# Tiles_Proto3_RevB.net
KiCad netlist of a schematic drawn in EAGLE
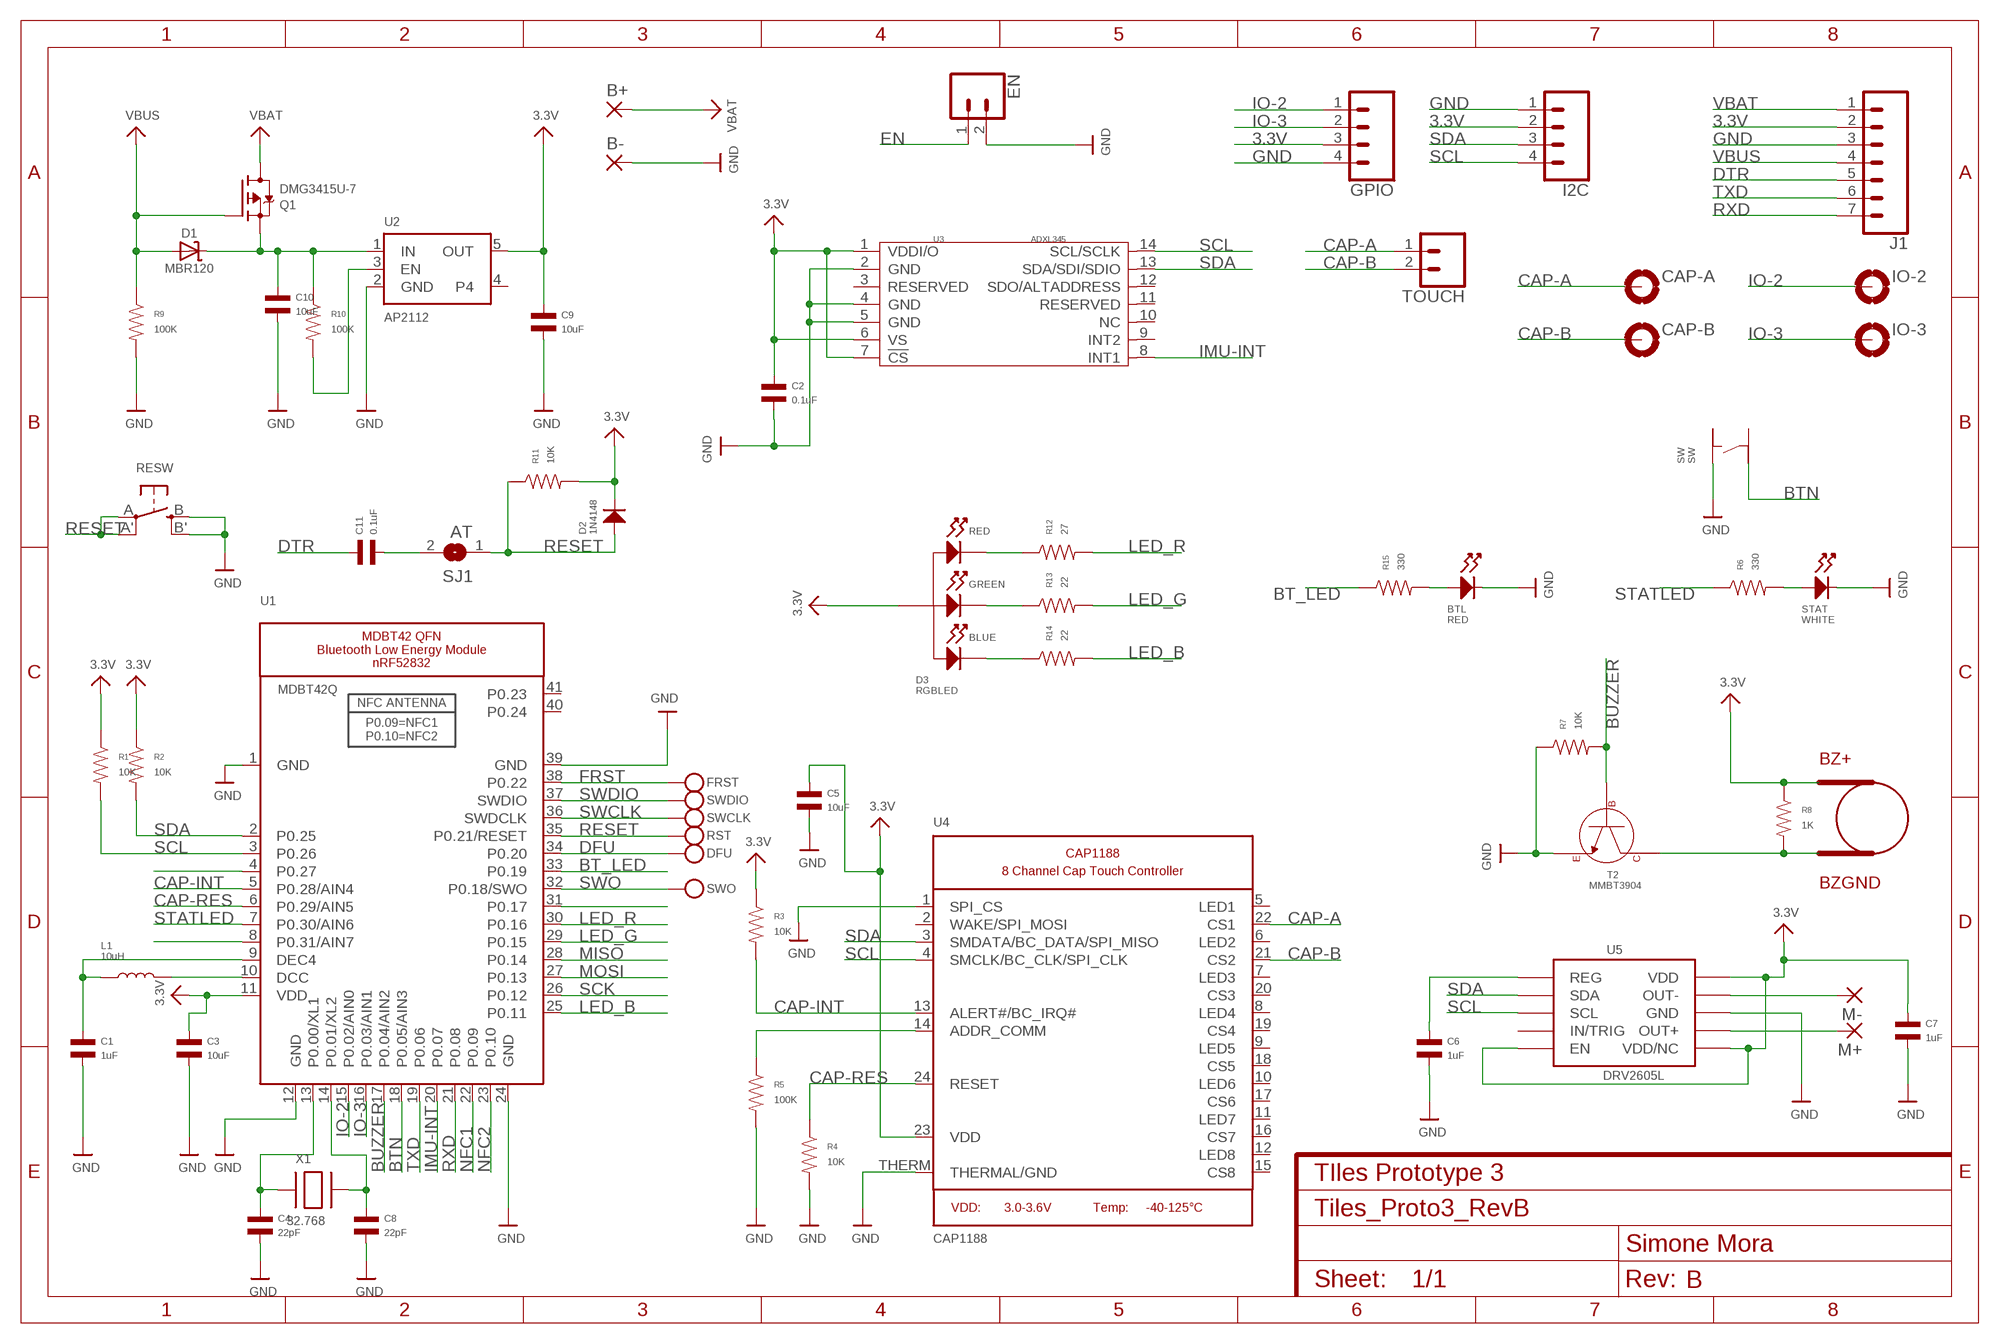
[diagram p0: schematic, sheet 1]

(export (version "E")
  (design (tool "Eeschema 10.0.6"))
  (components
    (comp (ref "B+")
      (value "SMD2")
      (footprint "eagle-import:SMD1,27-2,54")
      (libsource (lib "eagle-import") (part "SMD2"))
    )
    (comp (ref "B-")
      (value "SMD2")
      (footprint "eagle-import:SMD1,27-2,54")
      (libsource (lib "eagle-import") (part "SMD2"))
    )
    (comp (ref "BTL")
      (value "RED")
      (footprint "eagle-import:LED0603")
      (fields (field (name "HOUSEPART") "YES") (field (name "MPN") "MF-LED-0603-RED"))
      (libsource (lib "eagle-import") (part "LED_SINGLE-0603-RED"))
    )
    (comp (ref "BUZZER")
      (value "4MBUZ")
      (footprint "eagle-import:BUZPKG")
      (fields (field (name "HOUSEPART") "no") (field (name "MPN") "490-CMT-4023S-SMT-TR"))
      (libsource (lib "eagle-import") (part "4MBUZ"))
    )
    (comp (ref "C1")
      (value "1uF")
      (footprint "eagle-import:C0603")
      (fields (field (name "HOUSEPART") "YES") (field (name "MPN") "MF-CAP-0603-1uF"))
      (libsource (lib "eagle-import") (part "CAPACITOR_NP_0603"))
    )
    (comp (ref "C2")
      (value "0.1uF")
      (footprint "eagle-import:C0603")
      (fields (field (name "HOUSEPART") "YES") (field (name "MPN") "MF-CAP-0603-0.1uF"))
      (libsource (lib "eagle-import") (part "CAPACITOR_NP_0603"))
    )
    (comp (ref "C3")
      (value "10uF")
      (footprint "eagle-import:C1206")
      (fields (field (name "HOUSEPART") "YES") (field (name "MPN") "MF-CAP-1206-10uF"))
      (libsource (lib "eagle-import") (part "CAPACITOR_NP_1206"))
    )
    (comp (ref "C4")
      (value "22pF")
      (footprint "eagle-import:C0603")
      (fields (field (name "HOUSEPART") "YES") (field (name "MPN") "MF-CAP-0603-22pF"))
      (libsource (lib "eagle-import") (part "CAPACITOR_NP_0603"))
    )
    (comp (ref "C5")
      (value "10uF")
      (footprint "eagle-import:C1206")
      (fields (field (name "HOUSEPART") "YES") (field (name "MPN") "MF-CAP-1206-10uF"))
      (libsource (lib "eagle-import") (part "CAPACITOR_NP_1206"))
    )
    (comp (ref "C6")
      (value "1uF")
      (footprint "eagle-import:C0603")
      (fields (field (name "HOUSEPART") "YES") (field (name "MPN") "MF-CAP-0603-1uF"))
      (libsource (lib "eagle-import") (part "CAPACITOR_NP_0603"))
    )
    (comp (ref "C7")
      (value "1uF")
      (footprint "eagle-import:C0603")
      (fields (field (name "HOUSEPART") "YES") (field (name "MPN") "MF-CAP-0603-1uF"))
      (libsource (lib "eagle-import") (part "CAPACITOR_NP_0603"))
    )
    (comp (ref "C8")
      (value "22pF")
      (footprint "eagle-import:C0603")
      (fields (field (name "HOUSEPART") "YES") (field (name "MPN") "MF-CAP-0603-22pF"))
      (libsource (lib "eagle-import") (part "CAPACITOR_NP_0603"))
    )
    (comp (ref "C9")
      (value "10uF")
      (footprint "eagle-import:C1206")
      (fields (field (name "HOUSEPART") "YES") (field (name "MPN") "MF-CAP-1206-10uF"))
      (libsource (lib "eagle-import") (part "CAPACITOR_NP_1206"))
    )
    (comp (ref "C10")
      (value "10uF")
      (footprint "eagle-import:C1206")
      (fields (field (name "HOUSEPART") "YES") (field (name "MPN") "MF-CAP-1206-10uF"))
      (libsource (lib "eagle-import") (part "CAPACITOR_NP_1206"))
    )
    (comp (ref "C11")
      (value "0.1uF")
      (footprint "eagle-import:C0603")
      (fields (field (name "HOUSEPART") "YES") (field (name "MPN") "MF-CAP-0603-0.1uF"))
      (libsource (lib "eagle-import") (part "CAPACITOR_NP_0603"))
    )
    (comp (ref "CAP-A")
      (value "MOUNT-PAD-ROUND2.5")
      (footprint "eagle-import:2,5-PAD-SIM")
      (libsource (lib "eagle-import") (part "MOUNT-PAD-ROUND2.5"))
    )
    (comp (ref "CAP-B")
      (value "MOUNT-PAD-ROUND2.5")
      (footprint "eagle-import:2,5-PAD-SIM")
      (libsource (lib "eagle-import") (part "MOUNT-PAD-ROUND2.5"))
    )
    (comp (ref "D1")
      (value "MBR120")
      (footprint "eagle-import:SOD-123")
      (fields (field (name "HOUSEPART") "NO") (field (name "MPN") "MBR120LSFT1G"))
      (libsource (lib "eagle-import") (part "DIODE-SCHOTTKYSOD-123"))
    )
    (comp (ref "D2")
      (value "1N4148")
      (footprint "eagle-import:SOD-123")
      (fields (field (name "HOUSEPART") "YES") (field (name "MPN") "MF-DIO-SOD123-1N4148"))
      (libsource (lib "eagle-import") (part "DIODES_SOD-123_1N4148"))
    )
    (comp (ref "D3")
      (value "RGBLED")
      (footprint "eagle-import:PLCC4")
      (fields (field (name "HOUSEPART") "YES") (field (name "MPN") "MF-LED-3228-RGB"))
      (libsource (lib "eagle-import") (part "LED_RGB_CA_PLCC4"))
    )
    (comp (ref "DFU")
      (value "TESTPOINTROUND2MM")
      (footprint "eagle-import:TESTPOINT_ROUND_2MM")
      (libsource (lib "eagle-import") (part "TESTPOINTROUND2MM"))
    )
    (comp (ref "EN")
      (value "CONN_021X02_NO_SILK")
      (footprint "eagle-import:1X02_NO_SILK")
      (libsource (lib "eagle-import") (part "CONN_021X02_NO_SILK"))
    )
    (comp (ref "FRST")
      (value "TESTPOINT1.5X2.0MM_NOCREAM")
      (footprint "eagle-import:PAD-1.5X2.0")
      (libsource (lib "eagle-import") (part "TESTPOINT1.5X2.0MM_NOCREAM"))
    )
    (comp (ref "GPIO")
      (value "CONN_041X04_NO_SILK")
      (footprint "eagle-import:1X04_NO_SILK")
      (libsource (lib "eagle-import") (part "CONN_041X04_NO_SILK"))
    )
    (comp (ref "I2C")
      (value "CONN_04_SIM1X04_NO_SILK")
      (footprint "eagle-import:1X04_NO_SILK_LNG")
      (libsource (lib "eagle-import") (part "CONN_04_SIM1X04_NO_SILK"))
    )
    (comp (ref "IO-2")
      (value "MOUNT-PAD-ROUND2.5")
      (footprint "eagle-import:2,5-PAD-SIM")
      (libsource (lib "eagle-import") (part "MOUNT-PAD-ROUND2.5"))
    )
    (comp (ref "IO-3")
      (value "MOUNT-PAD-ROUND2.5")
      (footprint "eagle-import:2,5-PAD-SIM")
      (libsource (lib "eagle-import") (part "MOUNT-PAD-ROUND2.5"))
    )
    (comp (ref "J1")
      (value "CONN_07")
      (footprint "eagle-import:1X07")
      (libsource (lib "eagle-import") (part "CONN_07"))
    )
    (comp (ref "L1")
      (value "10uH")
      (footprint "eagle-import:L1210")
      (fields
        (field (name "HOUSEPART") "YES")
        (field (name "MPN") "MF-IND-1210-10uH")
        (field (name "POPULATE") "1")
      )
      (libsource (lib "eagle-import") (part "INDUCTOR_1210"))
    )
    (comp (ref "M+")
      (value "1,6/0,8")
      (footprint "eagle-import:1,6_0,8")
      (libsource (lib "eagle-import") (part "1,6/0,8"))
    )
    (comp (ref "M-")
      (value "1,6/0,8")
      (footprint "eagle-import:1,6_0,8")
      (libsource (lib "eagle-import") (part "1,6/0,8"))
    )
    (comp (ref "Q1")
      (value "DMG3415U-7")
      (footprint "eagle-import:SOT23-R")
      (fields (field (name "HOUSEPART") "YES") (field (name "MPN") "MF-DSC-SOT233-BSS84"))
      (libsource (lib "eagle-import") (part "MOSFET-P"))
    )
    (comp (ref "R1")
      (value "10K")
      (footprint "eagle-import:R0603")
      (fields (field (name "HOUSEPART") "YES") (field (name "MPN") "MF-RES-0603-10K"))
      (libsource (lib "eagle-import") (part "RESISTOR_0603"))
    )
    (comp (ref "R2")
      (value "10K")
      (footprint "eagle-import:R0603")
      (fields (field (name "HOUSEPART") "YES") (field (name "MPN") "MF-RES-0603-10K"))
      (libsource (lib "eagle-import") (part "RESISTOR_0603"))
    )
    (comp (ref "R3")
      (value "10K")
      (footprint "eagle-import:R0603")
      (fields (field (name "HOUSEPART") "YES") (field (name "MPN") "MF-RES-0603-10K"))
      (libsource (lib "eagle-import") (part "RESISTOR_0603"))
    )
    (comp (ref "R4")
      (value "10K")
      (footprint "eagle-import:R0603")
      (fields (field (name "HOUSEPART") "YES") (field (name "MPN") "MF-RES-0603-10K"))
      (libsource (lib "eagle-import") (part "RESISTOR_0603"))
    )
    (comp (ref "R5")
      (value "100K")
      (footprint "eagle-import:R0603")
      (fields (field (name "HOUSEPART") "YES") (field (name "MPN") "MF-RES-0603-100K"))
      (libsource (lib "eagle-import") (part "RESISTOR_0603"))
    )
    (comp (ref "R6")
      (value "330")
      (footprint "eagle-import:R0603")
      (fields (field (name "HOUSEPART") "YES") (field (name "MPN") "MF-RES-0603-330"))
      (libsource (lib "eagle-import") (part "RESISTOR_0603"))
    )
    (comp (ref "R7")
      (value "10K")
      (footprint "eagle-import:R0603")
      (fields (field (name "HOUSEPART") "YES") (field (name "MPN") "MF-RES-0603-10K"))
      (libsource (lib "eagle-import") (part "RESISTOR_0603"))
    )
    (comp (ref "R8")
      (value "1K")
      (footprint "eagle-import:R0603")
      (fields (field (name "HOUSEPART") "YES") (field (name "MPN") "MF-RES-0603-1K"))
      (libsource (lib "eagle-import") (part "RESISTOR_0603"))
    )
    (comp (ref "R9")
      (value "100K")
      (footprint "eagle-import:R0603")
      (fields (field (name "HOUSEPART") "YES") (field (name "MPN") "MF-RES-0603-100K"))
      (libsource (lib "eagle-import") (part "RESISTOR_0603"))
    )
    (comp (ref "R10")
      (value "100K")
      (footprint "eagle-import:R0603")
      (fields (field (name "HOUSEPART") "YES") (field (name "MPN") "MF-RES-0603-100K"))
      (libsource (lib "eagle-import") (part "RESISTOR_0603"))
    )
    (comp (ref "R11")
      (value "10K")
      (footprint "eagle-import:R0603")
      (fields (field (name "HOUSEPART") "YES") (field (name "MPN") "MF-RES-0603-10K"))
      (libsource (lib "eagle-import") (part "RESISTOR_0603"))
    )
    (comp (ref "R12")
      (value "27")
      (footprint "eagle-import:R0603")
      (fields (field (name "HOUSEPART") "YES") (field (name "MPN") "MF-RES-0603-27"))
      (libsource (lib "eagle-import") (part "RESISTOR_0603"))
    )
    (comp (ref "R13")
      (value "22")
      (footprint "eagle-import:R0603")
      (fields (field (name "HOUSEPART") "YES") (field (name "MPN") "MF-RES-0603-22"))
      (libsource (lib "eagle-import") (part "RESISTOR_0603"))
    )
    (comp (ref "R14")
      (value "22")
      (footprint "eagle-import:R0603")
      (fields (field (name "HOUSEPART") "YES") (field (name "MPN") "MF-RES-0603-22"))
      (libsource (lib "eagle-import") (part "RESISTOR_0603"))
    )
    (comp (ref "R15")
      (value "330")
      (footprint "eagle-import:R0603")
      (fields (field (name "HOUSEPART") "YES") (field (name "MPN") "MF-RES-0603-330"))
      (libsource (lib "eagle-import") (part "RESISTOR_0603"))
    )
    (comp (ref "RESW")
      (value "SWITCH_TACT_SMT4.6X2.8")
      (footprint "eagle-import:BTN_KMR2_4.6X2.8")
      (libsource (lib "eagle-import") (part "SWITCH_TACT_SMT4.6X2.8"))
    )
    (comp (ref "RST")
      (value "TESTPOINTROUND2MM")
      (footprint "eagle-import:TESTPOINT_ROUND_2MM")
      (libsource (lib "eagle-import") (part "TESTPOINTROUND2MM"))
    )
    (comp (ref "SJ1")
      (value "AT")
      (footprint "eagle-import:SOLDERJUMPER_CLOSEDWIRE")
      (libsource (lib "eagle-import") (part "SOLDERJUMPERCLOSED"))
    )
    (comp (ref "STAT")
      (value "WHITE")
      (footprint "eagle-import:LED0603")
      (fields
        (field (name "HOUSEPART") "YES")
        (field (name "MPN") "MF-LED-0603-RED")
        (field (name "HOUSEPART_1") "NO")
        (field (name "MPN_1") "LNJ037X8ARA")
      )
      (libsource (lib "eagle-import") (part "LED_SINGLE-0603-RED"))
    )
    (comp (ref "SW")
      (value "SW")
      (footprint "eagle-import:TACT4.2MM")
      (fields (field (name "HOUSEPART") "YES") (field (name "MPN") "MF-SW-TACT-4.2MM"))
      (libsource (lib "eagle-import") (part "TACT_4.2MM"))
    )
    (comp (ref "SWCLK")
      (value "TESTPOINTROUND2MM")
      (footprint "eagle-import:TESTPOINT_ROUND_2MM")
      (libsource (lib "eagle-import") (part "TESTPOINTROUND2MM"))
    )
    (comp (ref "SWDIO")
      (value "TESTPOINTROUND2MM")
      (footprint "eagle-import:TESTPOINT_ROUND_2MM")
      (libsource (lib "eagle-import") (part "TESTPOINTROUND2MM"))
    )
    (comp (ref "SWO")
      (value "TESTPOINTROUND2MM")
      (footprint "eagle-import:TESTPOINT_ROUND_2MM")
      (libsource (lib "eagle-import") (part "TESTPOINTROUND2MM"))
    )
    (comp (ref "T2")
      (value "MMBT3904")
      (footprint "eagle-import:SOT-23-3")
      (fields (field (name "HOUSEPART") "YES") (field (name "MPN") "MF-DSC-SOT233-MMBT3904"))
      (libsource (lib "eagle-import") (part "NPN_BJT_SOT-23-3MMBT3904"))
    )
    (comp (ref "TOUCH")
      (value "CONN_021X02_NO_SILK")
      (footprint "eagle-import:1X02_NO_SILK")
      (libsource (lib "eagle-import") (part "CONN_021X02_NO_SILK"))
    )
    (comp (ref "U1")
      (value "MDBT42Q")
      (footprint "eagle-import:BLE_MODULE_RAYTAC_MDBT42")
      (fields (field (name "HOUSEPART") "NO") (field (name "MPN") "317030213"))
      (libsource (lib "eagle-import") (part "NRF52832_MODULE_MDBT42"))
    )
    (comp (ref "U2")
      (value "AP2112")
      (footprint "eagle-import:SOT23-5")
      (fields (field (name "HOUSEPART") "NO") (field (name "MPN") "AP2112K-3.3TRG1"))
      (libsource (lib "eagle-import") (part "VREG_SOT23-5"))
    )
    (comp (ref "U3")
      (value "ADXL345")
      (footprint "eagle-import:LGA14-0.8-5.0X3.0MM")
      (fields (field (name "MPN") "ADXL345BCCZ-RL") (field (name "HOUSEPART") "no"))
      (libsource (lib "eagle-import") (part "MOTION/POSITION-ADXL345BCCZ-RL(14P-5.0X3.0MM)"))
    )
    (comp (ref "U4")
      (value "CAP1188")
      (footprint "eagle-import:QFN24_4MM_SMSC")
      (fields (field (name "HOUSEPART") "NO") (field (name "MPN") "CAP1188-1-CP-TR"))
      (libsource (lib "eagle-import") (part "CAP1188"))
    )
    (comp (ref "U5")
      (value "DRV2605L")
      (footprint "eagle-import:VSSOP-10")
      (fields (field (name "HOUSEPART") "NO") (field (name "MPN") "DRV2605LDGST"))
      (libsource (lib "eagle-import") (part "DRV2605L"))
    )
    (comp (ref "X1")
      (value "32.768")
      (footprint "eagle-import:XTAL3215")
      (fields (field (name "HOUSEPART") "no") (field (name "MPN") "ABS07-120-32.768KHZ-T"))
      (libsource (lib "eagle-import") (part "XTAL-3.2X1.5"))
    )
  )
  (nets
    (net (code "1") (name "/BTN") (class "Default")
      (node (ref "SW") (pin "P$3") (pinfunction "P$3_P$3") (pintype "bidirectional"))
      (node (ref "U1") (pin "18") (pinfunction "P0.05/AIN3_18") (pintype "bidirectional"))
    )
    (net (code "2") (name "/BT_LED") (class "Default")
      (node (ref "R15") (pin "P$1") (pinfunction "P$1_P$1") (pintype "passive"))
      (node (ref "U1") (pin "33") (pinfunction "P0.19_33") (pintype "bidirectional"))
    )
    (net (code "3") (name "/BUZZER") (class "Default")
      (node (ref "R7") (pin "P$2") (pinfunction "P$2_P$2") (pintype "passive"))
      (node (ref "T2") (pin "P$1") (pinfunction "BASE_P$1") (pintype "bidirectional"))
      (node (ref "U1") (pin "17") (pinfunction "P0.04/AIN2_17") (pintype "bidirectional"))
    )
    (net (code "4") (name "/CAP-A") (class "Default")
      (node (ref "CAP-A") (pin "B2,8") (pinfunction "MOUNT_B2,8") (pintype "passive"))
      (node (ref "TOUCH") (pin "1") (pinfunction "1_1") (pintype "passive"))
      (node (ref "U4") (pin "22") (pinfunction "CS1_22") (pintype "bidirectional"))
    )
    (net (code "5") (name "/CAP-B") (class "Default")
      (node (ref "CAP-B") (pin "B2,8") (pinfunction "MOUNT_B2,8") (pintype "passive"))
      (node (ref "TOUCH") (pin "2") (pinfunction "2_2") (pintype "passive"))
      (node (ref "U4") (pin "21") (pinfunction "CS2_21") (pintype "bidirectional"))
    )
    (net (code "6") (name "/CAP-INT") (class "Default")
      (node (ref "R3") (pin "P$2") (pinfunction "P$2_P$2") (pintype "passive"))
      (node (ref "U1") (pin "5") (pinfunction "P0.28/AIN4_5") (pintype "bidirectional"))
      (node (ref "U4") (pin "13") (pinfunction "ALERT#/BC_IRQ#_13") (pintype "bidirectional"))
    )
    (net (code "7") (name "/CAP-RES") (class "Default")
      (node (ref "R4") (pin "P$1") (pinfunction "P$1_P$1") (pintype "passive"))
      (node (ref "U1") (pin "6") (pinfunction "P0.29/AIN5_6") (pintype "bidirectional"))
      (node (ref "U4") (pin "24") (pinfunction "RESET_24") (pintype "input"))
    )
    (net (code "8") (name "/DFU") (class "Default")
      (node (ref "DFU") (pin "P$1") (pinfunction "P$1_P$1") (pintype "bidirectional"))
      (node (ref "U1") (pin "34") (pinfunction "P0.20_34") (pintype "bidirectional"))
    )
    (net (code "9") (name "/DTR") (class "Default")
      (node (ref "C11") (pin "P$1") (pinfunction "P$1_P$1") (pintype "passive"))
      (node (ref "J1") (pin "5") (pinfunction "5_5") (pintype "passive"))
    )
    (net (code "10") (name "/EN") (class "Default")
      (node (ref "EN") (pin "1") (pinfunction "1_1") (pintype "passive"))
      (node (ref "R10") (pin "P$2") (pinfunction "P$2_P$2") (pintype "passive"))
      (node (ref "U2") (pin "3") (pinfunction "EN_3") (pintype "input"))
    )
    (net (code "11") (name "/FRST") (class "Default")
      (node (ref "FRST") (pin "P$1") (pinfunction "P$1_P$1") (pintype "bidirectional"))
      (node (ref "U1") (pin "38") (pinfunction "P0.22_38") (pintype "bidirectional"))
    )
    (net (code "12") (name "/IMU-INT") (class "Default")
      (node (ref "U1") (pin "20") (pinfunction "P0.07_20") (pintype "bidirectional"))
      (node (ref "U3") (pin "8") (pinfunction "INT1_8") (pintype "bidirectional"))
    )
    (net (code "13") (name "/IO-2") (class "Default")
      (node (ref "GPIO") (pin "1") (pinfunction "1_1") (pintype "passive"))
      (node (ref "IO-2") (pin "B2,8") (pinfunction "MOUNT_B2,8") (pintype "passive"))
      (node (ref "U1") (pin "15") (pinfunction "P0.02/AIN0_15") (pintype "bidirectional"))
    )
    (net (code "14") (name "/IO-3") (class "Default")
      (node (ref "GPIO") (pin "2") (pinfunction "2_2") (pintype "passive"))
      (node (ref "IO-3") (pin "B2,8") (pinfunction "MOUNT_B2,8") (pintype "passive"))
      (node (ref "U1") (pin "16") (pinfunction "P0.03/AIN1_16") (pintype "bidirectional"))
    )
    (net (code "15") (name "/LED_B") (class "Default")
      (node (ref "R14") (pin "P$2") (pinfunction "P$2_P$2") (pintype "passive"))
      (node (ref "U1") (pin "25") (pinfunction "P0.11_25") (pintype "bidirectional"))
    )
    (net (code "16") (name "/LED_G") (class "Default")
      (node (ref "R13") (pin "P$2") (pinfunction "P$2_P$2") (pintype "passive"))
      (node (ref "U1") (pin "29") (pinfunction "P0.15_29") (pintype "bidirectional"))
    )
    (net (code "17") (name "/LED_R") (class "Default")
      (node (ref "R12") (pin "P$2") (pinfunction "P$2_P$2") (pintype "passive"))
      (node (ref "U1") (pin "30") (pinfunction "P0.16_30") (pintype "bidirectional"))
    )
    (net (code "18") (name "/MISO") (class "Default")
      (node (ref "U1") (pin "28") (pinfunction "P0.14_28") (pintype "bidirectional"))
    )
    (net (code "19") (name "/MOSI") (class "Default")
      (node (ref "U1") (pin "27") (pinfunction "P0.13_27") (pintype "bidirectional"))
    )
    (net (code "20") (name "/NFC1") (class "Default")
      (node (ref "U1") (pin "22") (pinfunction "P0.09_22") (pintype "bidirectional"))
    )
    (net (code "21") (name "/NFC2") (class "Default")
      (node (ref "U1") (pin "23") (pinfunction "P0.10_23") (pintype "bidirectional"))
    )
    (net (code "22") (name "/RESET") (class "Default")
      (node (ref "D2") (pin "ANODE") (pinfunction "ANODE_ANODE") (pintype "bidirectional"))
      (node (ref "R11") (pin "P$1") (pinfunction "P$1_P$1") (pintype "passive"))
      (node (ref "RESW") (pin "A") (pinfunction "P_A") (pintype "passive"))
      (node (ref "RESW") (pin "A'") (pinfunction "P1_A'") (pintype "passive"))
      (node (ref "RST") (pin "P$1") (pinfunction "P$1_P$1") (pintype "bidirectional"))
      (node (ref "SJ1") (pin "1") (pinfunction "1_1") (pintype "passive"))
      (node (ref "U1") (pin "35") (pinfunction "P0.21/RESET_35") (pintype "bidirectional"))
    )
    (net (code "23") (name "/RXD") (class "Default")
      (node (ref "J1") (pin "7") (pinfunction "7_7") (pintype "passive"))
      (node (ref "U1") (pin "21") (pinfunction "P0.08_21") (pintype "bidirectional"))
    )
    (net (code "24") (name "/SCK") (class "Default")
      (node (ref "U1") (pin "26") (pinfunction "P0.12_26") (pintype "bidirectional"))
    )
    (net (code "25") (name "/SCL") (class "Default")
      (node (ref "I2C") (pin "4") (pinfunction "4_4") (pintype "passive"))
      (node (ref "R1") (pin "P$2") (pinfunction "P$2_P$2") (pintype "passive"))
      (node (ref "U1") (pin "3") (pinfunction "P0.26_3") (pintype "bidirectional"))
      (node (ref "U3") (pin "14") (pinfunction "SCL/SCLK_14") (pintype "input"))
      (node (ref "U4") (pin "4") (pinfunction "SMCLK/BC_CLK/SPI_CLK_4") (pintype "bidirectional"))
      (node (ref "U5") (pin "P$2") (pinfunction "SCL_P$2") (pintype "bidirectional"))
    )
    (net (code "26") (name "/SDA") (class "Default")
      (node (ref "I2C") (pin "3") (pinfunction "3_3") (pintype "passive"))
      (node (ref "R2") (pin "P$2") (pinfunction "P$2_P$2") (pintype "passive"))
      (node (ref "U1") (pin "2") (pinfunction "P0.25_2") (pintype "bidirectional"))
      (node (ref "U3") (pin "13") (pinfunction "SDA/SDI/SDIO_13") (pintype "bidirectional"))
      (node (ref "U4") (pin "3") (pinfunction "SMDATA/BC_DATA/SPI_MISO_3") (pintype "bidirectional"))
      (node (ref "U5") (pin "P$3") (pinfunction "SDA_P$3") (pintype "bidirectional"))
    )
    (net (code "27") (name "/STATLED") (class "Default")
      (node (ref "R6") (pin "P$1") (pinfunction "P$1_P$1") (pintype "passive"))
      (node (ref "U1") (pin "7") (pinfunction "P0.30/AIN6_7") (pintype "bidirectional"))
    )
    (net (code "28") (name "/SWCLK") (class "Default")
      (node (ref "SWCLK") (pin "P$1") (pinfunction "P$1_P$1") (pintype "bidirectional"))
      (node (ref "U1") (pin "36") (pinfunction "SWDCLK_36") (pintype "bidirectional"))
    )
    (net (code "29") (name "/SWDIO") (class "Default")
      (node (ref "SWDIO") (pin "P$1") (pinfunction "P$1_P$1") (pintype "bidirectional"))
      (node (ref "U1") (pin "37") (pinfunction "SWDIO_37") (pintype "bidirectional"))
    )
    (net (code "30") (name "/SWO") (class "Default")
      (node (ref "SWO") (pin "P$1") (pinfunction "P$1_P$1") (pintype "bidirectional"))
      (node (ref "U1") (pin "32") (pinfunction "P0.18/SWO_32") (pintype "bidirectional"))
    )
    (net (code "31") (name "/TXD") (class "Default")
      (node (ref "J1") (pin "6") (pinfunction "6_6") (pintype "passive"))
      (node (ref "U1") (pin "19") (pinfunction "P0.06_19") (pintype "bidirectional"))
    )
    (net (code "32") (name "3.3V") (class "Default")
      (node (ref "BUZZER") (pin "BZ+") (pinfunction "BUZSIG+_BZ+") (pintype "passive"))
      (node (ref "C2") (pin "P$1") (pinfunction "P$1_P$1") (pintype "passive"))
      (node (ref "C3") (pin "P$1") (pinfunction "P$1_P$1") (pintype "passive"))
      (node (ref "C5") (pin "P$1") (pinfunction "P$1_P$1") (pintype "passive"))
      (node (ref "C7") (pin "P$1") (pinfunction "P$1_P$1") (pintype "passive"))
      (node (ref "C9") (pin "P$1") (pinfunction "P$1_P$1") (pintype "passive"))
      (node (ref "D2") (pin "CATHODE") (pinfunction "CATHODE_CATHODE") (pintype "bidirectional"))
      (node (ref "D3") (pin "P$1") (pinfunction "ANODE_P$1") (pintype "power_in"))
      (node (ref "GPIO") (pin "3") (pinfunction "3_3") (pintype "passive"))
      (node (ref "I2C") (pin "2") (pinfunction "2_2") (pintype "passive"))
      (node (ref "J1") (pin "2") (pinfunction "2_2") (pintype "passive"))
      (node (ref "R1") (pin "P$1") (pinfunction "P$1_P$1") (pintype "passive"))
      (node (ref "R11") (pin "P$2") (pinfunction "P$2_P$2") (pintype "passive"))
      (node (ref "R2") (pin "P$1") (pinfunction "P$1_P$1") (pintype "passive"))
      (node (ref "R3") (pin "P$1") (pinfunction "P$1_P$1") (pintype "passive"))
      (node (ref "R8") (pin "P$1") (pinfunction "P$1_P$1") (pintype "passive"))
      (node (ref "U1") (pin "11") (pinfunction "VDD_11") (pintype "bidirectional"))
      (node (ref "U2") (pin "5") (pinfunction "OUT_5") (pintype "power_in"))
      (node (ref "U3") (pin "1") (pinfunction "VDDI/O_1") (pintype "power_in"))
      (node (ref "U3") (pin "6") (pinfunction "VS_6") (pintype "bidirectional"))
      (node (ref "U3") (pin "7") (pinfunction "~{CS}_7") (pintype "bidirectional"))
      (node (ref "U4") (pin "23") (pinfunction "VDD_23") (pintype "power_in"))
      (node (ref "U5") (pin "P$10") (pinfunction "VDD_P$10") (pintype "bidirectional"))
      (node (ref "U5") (pin "P$5") (pinfunction "EN_P$5") (pintype "bidirectional"))
      (node (ref "U5") (pin "P$6") (pinfunction "VDD/NC_P$6") (pintype "bidirectional"))
    )
    (net (code "33") (name "GND") (class "Default")
      (node (ref "B-") (pin "1") (pinfunction "P_1") (pintype "passive"))
      (node (ref "BTL") (pin "CATHODE") (pinfunction "CATHODE_CATHODE") (pintype "power_in"))
      (node (ref "C1") (pin "P$2") (pinfunction "P$2_P$2") (pintype "passive"))
      (node (ref "C10") (pin "P$2") (pinfunction "P$2_P$2") (pintype "passive"))
      (node (ref "C2") (pin "P$2") (pinfunction "P$2_P$2") (pintype "passive"))
      (node (ref "C3") (pin "P$2") (pinfunction "P$2_P$2") (pintype "passive"))
      (node (ref "C4") (pin "P$2") (pinfunction "P$2_P$2") (pintype "passive"))
      (node (ref "C5") (pin "P$2") (pinfunction "P$2_P$2") (pintype "passive"))
      (node (ref "C6") (pin "P$2") (pinfunction "P$2_P$2") (pintype "passive"))
      (node (ref "C7") (pin "P$2") (pinfunction "P$2_P$2") (pintype "passive"))
      (node (ref "C8") (pin "P$2") (pinfunction "P$2_P$2") (pintype "passive"))
      (node (ref "C9") (pin "P$2") (pinfunction "P$2_P$2") (pintype "passive"))
      (node (ref "EN") (pin "2") (pinfunction "2_2") (pintype "passive"))
      (node (ref "GPIO") (pin "4") (pinfunction "4_4") (pintype "passive"))
      (node (ref "I2C") (pin "1") (pinfunction "1_1") (pintype "passive"))
      (node (ref "J1") (pin "3") (pinfunction "3_3") (pintype "passive"))
      (node (ref "R4") (pin "P$2") (pinfunction "P$2_P$2") (pintype "passive"))
      (node (ref "R5") (pin "P$2") (pinfunction "P$2_P$2") (pintype "passive"))
      (node (ref "R7") (pin "P$1") (pinfunction "P$1_P$1") (pintype "passive"))
      (node (ref "R9") (pin "P$2") (pinfunction "P$2_P$2") (pintype "passive"))
      (node (ref "RESW") (pin "B") (pinfunction "S_B") (pintype "passive"))
      (node (ref "RESW") (pin "B'") (pinfunction "S1_B'") (pintype "passive"))
      (node (ref "STAT") (pin "CATHODE") (pinfunction "CATHODE_CATHODE") (pintype "power_in"))
      (node (ref "SW") (pin "P$1") (pinfunction "P$1_P$1") (pintype "bidirectional"))
      (node (ref "T2") (pin "P$2") (pinfunction "EMITTER_P$2") (pintype "bidirectional"))
      (node (ref "U1") (pin "1") (pinfunction "GND_1") (pintype "bidirectional"))
      (node (ref "U1") (pin "12") (pinfunction "GND_12") (pintype "bidirectional"))
      (node (ref "U1") (pin "24") (pinfunction "GND_24") (pintype "bidirectional"))
      (node (ref "U1") (pin "39") (pinfunction "GND_39") (pintype "bidirectional"))
      (node (ref "U2") (pin "2") (pinfunction "GND_2") (pintype "power_in"))
      (node (ref "U3") (pin "2") (pinfunction "GND_2") (pintype "power_in"))
      (node (ref "U3") (pin "4") (pinfunction "GND_4") (pintype "power_in"))
      (node (ref "U3") (pin "5") (pinfunction "GND_5") (pintype "power_in"))
      (node (ref "U4") (pin "1") (pinfunction "SPI_CS_1") (pintype "input"))
      (node (ref "U4") (pin "THERM") (pinfunction "THERMAL/GND_THERM") (pintype "power_in"))
      (node (ref "U5") (pin "P$8") (pinfunction "GND_P$8") (pintype "bidirectional"))
    )
    (net (code "34") (name "Net-(BTL-PadANODE)") (class "Default")
      (node (ref "BTL") (pin "ANODE") (pinfunction "ANODE_ANODE") (pintype "power_in"))
      (node (ref "R15") (pin "P$2") (pinfunction "P$2_P$2") (pintype "passive"))
    )
    (net (code "35") (name "Net-(BUZZER-BUZGND)") (class "Default")
      (node (ref "BUZZER") (pin "BZ-") (pinfunction "BUZGND_BZ-") (pintype "passive"))
      (node (ref "R8") (pin "P$2") (pinfunction "P$2_P$2") (pintype "passive"))
      (node (ref "T2") (pin "P$3") (pinfunction "COLLECTOR_P$3") (pintype "bidirectional"))
    )
    (net (code "36") (name "Net-(C11-PadP$2)") (class "Default")
      (node (ref "C11") (pin "P$2") (pinfunction "P$2_P$2") (pintype "passive"))
      (node (ref "SJ1") (pin "2") (pinfunction "2_2") (pintype "passive"))
    )
    (net (code "37") (name "Net-(D3-CATHODE_BLUE)") (class "Default")
      (node (ref "D3") (pin "P$4") (pinfunction "CATHODE_BLUE_P$4") (pintype "power_in"))
      (node (ref "R14") (pin "P$1") (pinfunction "P$1_P$1") (pintype "passive"))
    )
    (net (code "38") (name "Net-(D3-CATHODE_GREEN)") (class "Default")
      (node (ref "D3") (pin "P$3") (pinfunction "CATHODE_GREEN_P$3") (pintype "power_in"))
      (node (ref "R13") (pin "P$1") (pinfunction "P$1_P$1") (pintype "passive"))
    )
    (net (code "39") (name "Net-(D3-CATHODE_RED)") (class "Default")
      (node (ref "D3") (pin "P$2") (pinfunction "CATHODE_RED_P$2") (pintype "power_in"))
      (node (ref "R12") (pin "P$1") (pinfunction "P$1_P$1") (pintype "passive"))
    )
    (net (code "40") (name "Net-(M+-P)") (class "Default")
      (node (ref "M+") (pin "1") (pinfunction "P_1") (pintype "passive"))
      (node (ref "U5") (pin "P$7") (pinfunction "OUT+_P$7") (pintype "bidirectional"))
    )
    (net (code "41") (name "Net-(M--P)") (class "Default")
      (node (ref "M-") (pin "1") (pinfunction "P_1") (pintype "passive"))
      (node (ref "U5") (pin "P$9") (pinfunction "OUT-_P$9") (pintype "bidirectional"))
    )
    (net (code "42") (name "Net-(Q1-S)") (class "Default")
      (node (ref "C10") (pin "P$1") (pinfunction "P$1_P$1") (pintype "passive"))
      (node (ref "D1") (pin "C") (pinfunction "C_C") (pintype "passive"))
      (node (ref "Q1") (pin "2") (pinfunction "S_2") (pintype "passive"))
      (node (ref "R10") (pin "P$1") (pinfunction "P$1_P$1") (pintype "passive"))
      (node (ref "U2") (pin "1") (pinfunction "IN_1") (pintype "power_in"))
    )
    (net (code "43") (name "Net-(R6-PadP$2)") (class "Default")
      (node (ref "R6") (pin "P$2") (pinfunction "P$2_P$2") (pintype "passive"))
      (node (ref "STAT") (pin "ANODE") (pinfunction "ANODE_ANODE") (pintype "power_in"))
    )
    (net (code "44") (name "Net-(U1-DCC)") (class "Default")
      (node (ref "L1") (pin "P$2") (pinfunction "P$2_P$2") (pintype "passive"))
      (node (ref "U1") (pin "10") (pinfunction "DCC_10") (pintype "bidirectional"))
    )
    (net (code "45") (name "Net-(U1-DEC4)") (class "Default")
      (node (ref "C1") (pin "P$1") (pinfunction "P$1_P$1") (pintype "passive"))
      (node (ref "L1") (pin "P$1") (pinfunction "P$1_P$1") (pintype "passive"))
      (node (ref "U1") (pin "9") (pinfunction "DEC4_9") (pintype "bidirectional"))
    )
    (net (code "46") (name "Net-(U1-P0.00{slash}XL1)") (class "Default")
      (node (ref "C4") (pin "P$1") (pinfunction "P$1_P$1") (pintype "passive"))
      (node (ref "U1") (pin "13") (pinfunction "P0.00/XL1_13") (pintype "bidirectional"))
      (node (ref "X1") (pin "P$1") (pinfunction "P$1_P$1") (pintype "bidirectional"))
    )
    (net (code "47") (name "Net-(U1-P0.01{slash}XL2)") (class "Default")
      (node (ref "C8") (pin "P$1") (pinfunction "P$1_P$1") (pintype "passive"))
      (node (ref "U1") (pin "14") (pinfunction "P0.01/XL2_14") (pintype "bidirectional"))
      (node (ref "X1") (pin "P$2") (pinfunction "P$2_P$2") (pintype "bidirectional"))
    )
    (net (code "48") (name "Net-(U4-ADDR_COMM)") (class "Default")
      (node (ref "R5") (pin "P$1") (pinfunction "P$1_P$1") (pintype "passive"))
      (node (ref "U4") (pin "14") (pinfunction "ADDR_COMM_14") (pintype "bidirectional"))
    )
    (net (code "49") (name "Net-(U5-REG)") (class "Default")
      (node (ref "C6") (pin "P$1") (pinfunction "P$1_P$1") (pintype "passive"))
      (node (ref "U5") (pin "P$1") (pinfunction "REG_P$1") (pintype "bidirectional"))
    )
    (net (code "50") (name "VBAT") (class "Default")
      (node (ref "B+") (pin "1") (pinfunction "P_1") (pintype "passive"))
      (node (ref "J1") (pin "1") (pinfunction "1_1") (pintype "passive"))
      (node (ref "Q1") (pin "3") (pinfunction "D_3") (pintype "passive"))
    )
    (net (code "51") (name "VBUS") (class "Default")
      (node (ref "D1") (pin "A") (pinfunction "A_A") (pintype "passive"))
      (node (ref "J1") (pin "4") (pinfunction "4_4") (pintype "passive"))
      (node (ref "Q1") (pin "1") (pinfunction "G_1") (pintype "passive"))
      (node (ref "R9") (pin "P$1") (pinfunction "P$1_P$1") (pintype "passive"))
    )
    (net (code "52") (name "unconnected-(SW-PadP$2)") (class "Default")
      (node (ref "SW") (pin "P$2") (pinfunction "P$2_P$2") (pintype "bidirectional"))
    )
    (net (code "53") (name "unconnected-(SW-PadP$4)") (class "Default")
      (node (ref "SW") (pin "P$4") (pinfunction "P$4_P$4") (pintype "bidirectional"))
    )
    (net (code "54") (name "unconnected-(U1-P0.17-Pad31)") (class "Default")
      (node (ref "U1") (pin "31") (pinfunction "P0.17_31") (pintype "bidirectional"))
    )
    (net (code "55") (name "unconnected-(U1-P0.23-Pad41)") (class "Default")
      (node (ref "U1") (pin "41") (pinfunction "P0.23_41") (pintype "bidirectional"))
    )
    (net (code "56") (name "unconnected-(U1-P0.24-Pad40)") (class "Default")
      (node (ref "U1") (pin "40") (pinfunction "P0.24_40") (pintype "bidirectional"))
    )
    (net (code "57") (name "unconnected-(U1-P0.27-Pad4)") (class "Default")
      (node (ref "U1") (pin "4") (pinfunction "P0.27_4") (pintype "bidirectional"))
    )
    (net (code "58") (name "unconnected-(U1-P0.31{slash}AIN7-Pad8)") (class "Default")
      (node (ref "U1") (pin "8") (pinfunction "P0.31/AIN7_8") (pintype "bidirectional"))
    )
    (net (code "59") (name "unconnected-(U2-P4-Pad4)") (class "Default")
      (node (ref "U2") (pin "4") (pinfunction "P4_4") (pintype "bidirectional"))
    )
    (net (code "60") (name "unconnected-(U3-INT2-Pad9)") (class "Default")
      (node (ref "U3") (pin "9") (pinfunction "INT2_9") (pintype "bidirectional"))
    )
    (net (code "61") (name "unconnected-(U3-NC-Pad10)") (class "Default")
      (node (ref "U3") (pin "10") (pinfunction "NC_10") (pintype "no_connect"))
    )
    (net (code "62") (name "unconnected-(U3-RESERVED-Pad3)") (class "Default")
      (node (ref "U3") (pin "3") (pinfunction "RESERVED_3") (pintype "bidirectional"))
    )
    (net (code "63") (name "unconnected-(U3-RESERVED-Pad11)") (class "Default")
      (node (ref "U3") (pin "11") (pinfunction "RESERVED_11") (pintype "bidirectional"))
    )
    (net (code "64") (name "unconnected-(U3-SDO{slash}ALTADDRESS-Pad12)") (class "Default")
      (node (ref "U3") (pin "12") (pinfunction "SDO/ALTADDRESS_12") (pintype "bidirectional"))
    )
    (net (code "65") (name "unconnected-(U4-CS3-Pad20)") (class "Default")
      (node (ref "U4") (pin "20") (pinfunction "CS3_20") (pintype "bidirectional"))
    )
    (net (code "66") (name "unconnected-(U4-CS4-Pad19)") (class "Default")
      (node (ref "U4") (pin "19") (pinfunction "CS4_19") (pintype "bidirectional"))
    )
    (net (code "67") (name "unconnected-(U4-CS5-Pad18)") (class "Default")
      (node (ref "U4") (pin "18") (pinfunction "CS5_18") (pintype "bidirectional"))
    )
    (net (code "68") (name "unconnected-(U4-CS6-Pad17)") (class "Default")
      (node (ref "U4") (pin "17") (pinfunction "CS6_17") (pintype "bidirectional"))
    )
    (net (code "69") (name "unconnected-(U4-CS7-Pad16)") (class "Default")
      (node (ref "U4") (pin "16") (pinfunction "CS7_16") (pintype "bidirectional"))
    )
    (net (code "70") (name "unconnected-(U4-CS8-Pad15)") (class "Default")
      (node (ref "U4") (pin "15") (pinfunction "CS8_15") (pintype "bidirectional"))
    )
    (net (code "71") (name "unconnected-(U4-LED1-Pad5)") (class "Default")
      (node (ref "U4") (pin "5") (pinfunction "LED1_5") (pintype "bidirectional"))
    )
    (net (code "72") (name "unconnected-(U4-LED2-Pad6)") (class "Default")
      (node (ref "U4") (pin "6") (pinfunction "LED2_6") (pintype "bidirectional"))
    )
    (net (code "73") (name "unconnected-(U4-LED3-Pad7)") (class "Default")
      (node (ref "U4") (pin "7") (pinfunction "LED3_7") (pintype "bidirectional"))
    )
    (net (code "74") (name "unconnected-(U4-LED4-Pad8)") (class "Default")
      (node (ref "U4") (pin "8") (pinfunction "LED4_8") (pintype "bidirectional"))
    )
    (net (code "75") (name "unconnected-(U4-LED5-Pad9)") (class "Default")
      (node (ref "U4") (pin "9") (pinfunction "LED5_9") (pintype "bidirectional"))
    )
    (net (code "76") (name "unconnected-(U4-LED6-Pad10)") (class "Default")
      (node (ref "U4") (pin "10") (pinfunction "LED6_10") (pintype "bidirectional"))
    )
    (net (code "77") (name "unconnected-(U4-LED7-Pad11)") (class "Default")
      (node (ref "U4") (pin "11") (pinfunction "LED7_11") (pintype "bidirectional"))
    )
    (net (code "78") (name "unconnected-(U4-LED8-Pad12)") (class "Default")
      (node (ref "U4") (pin "12") (pinfunction "LED8_12") (pintype "bidirectional"))
    )
    (net (code "79") (name "unconnected-(U4-WAKE{slash}SPI_MOSI-Pad2)") (class "Default")
      (node (ref "U4") (pin "2") (pinfunction "WAKE/SPI_MOSI_2") (pintype "bidirectional"))
    )
    (net (code "80") (name "unconnected-(U5-IN{slash}TRIG-PadP$4)") (class "Default")
      (node (ref "U5") (pin "P$4") (pinfunction "IN/TRIG_P$4") (pintype "bidirectional"))
    )
  )
)
